# SplitterBoxRevA.net
KiCad netlist of a schematic drawn in EAGLE
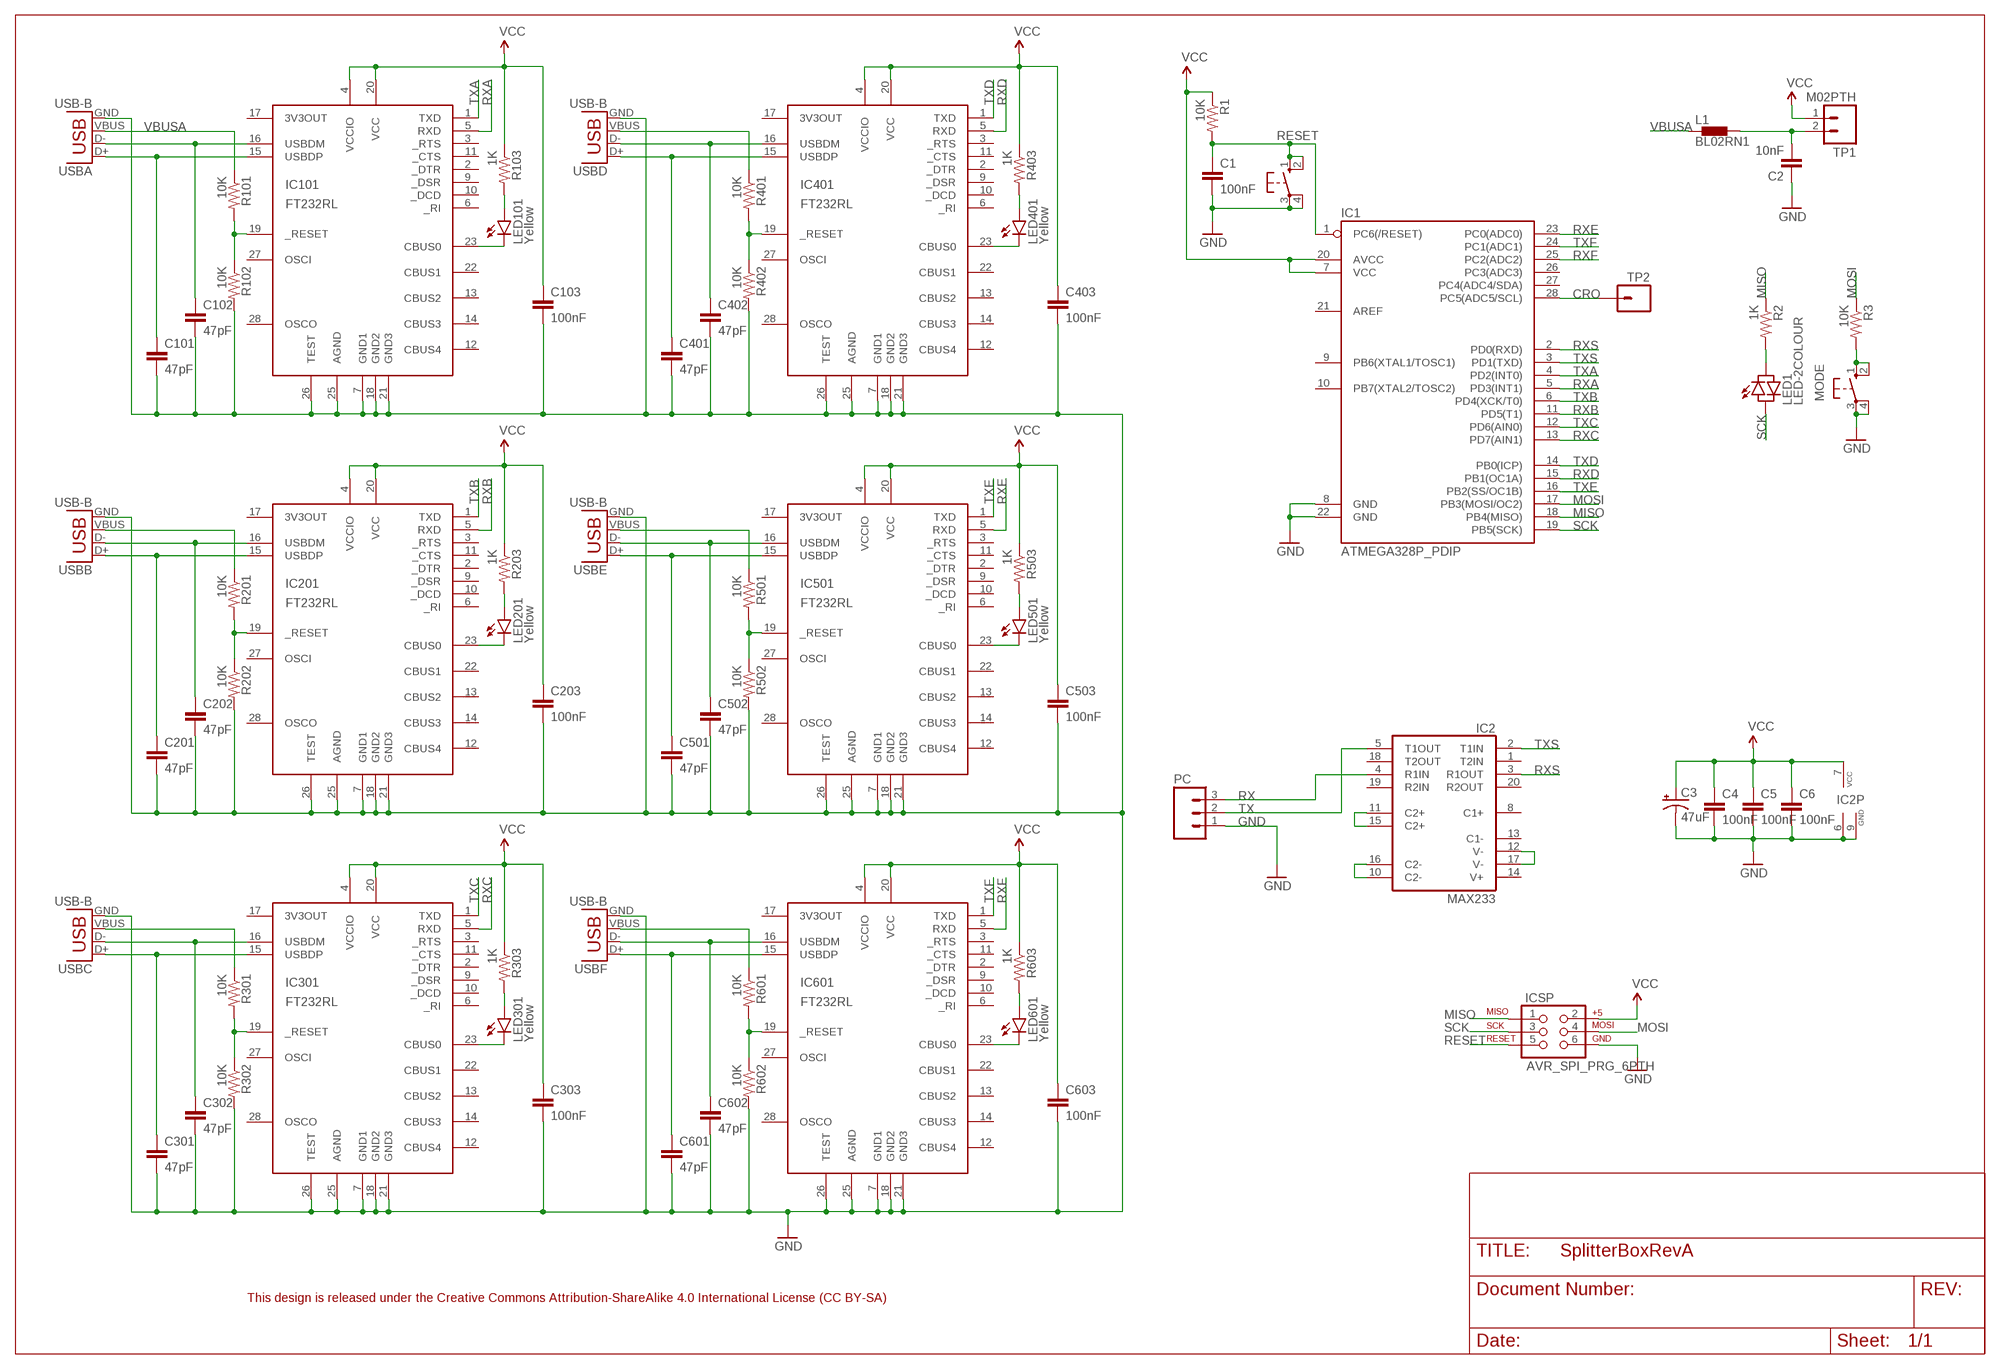
[diagram p0: schematic, sheet 1]

(export (version "E")
  (design (tool "Eeschema 10.0.6"))
  (components
    (comp (ref "C1")
      (value "100nF")
      (footprint "eagle-import:CAP-PTH-SMALL")
      (libsource (lib "eagle-import") (part "CAPPTH"))
    )
    (comp (ref "C2")
      (value "10nF")
      (footprint "eagle-import:CAP-PTH-SMALL")
      (libsource (lib "eagle-import") (part "CAPPTH"))
    )
    (comp (ref "C3")
      (value "47uF")
      (footprint "eagle-import:CPOL-RADIAL-100UF-25V")
      (libsource (lib "eagle-import") (part "CAP_POLPTH1"))
    )
    (comp (ref "C4")
      (value "100nF")
      (footprint "eagle-import:CAP-PTH-SMALL")
      (libsource (lib "eagle-import") (part "CAPPTH"))
    )
    (comp (ref "C5")
      (value "100nF")
      (footprint "eagle-import:CAP-PTH-SMALL")
      (libsource (lib "eagle-import") (part "CAPPTH"))
    )
    (comp (ref "C6")
      (value "100nF")
      (footprint "eagle-import:CAP-PTH-SMALL")
      (libsource (lib "eagle-import") (part "CAPPTH"))
    )
    (comp (ref "C101")
      (value "47pF")
      (footprint "eagle-import:CAP-PTH-SMALL")
      (libsource (lib "eagle-import") (part "CAPPTH"))
    )
    (comp (ref "C102")
      (value "47pF")
      (footprint "eagle-import:CAP-PTH-SMALL")
      (libsource (lib "eagle-import") (part "CAPPTH"))
    )
    (comp (ref "C103")
      (value "100nF")
      (footprint "eagle-import:CAP-PTH-SMALL")
      (libsource (lib "eagle-import") (part "CAPPTH"))
    )
    (comp (ref "C201")
      (value "47pF")
      (footprint "eagle-import:CAP-PTH-SMALL")
      (libsource (lib "eagle-import") (part "CAPPTH"))
    )
    (comp (ref "C202")
      (value "47pF")
      (footprint "eagle-import:CAP-PTH-SMALL")
      (libsource (lib "eagle-import") (part "CAPPTH"))
    )
    (comp (ref "C203")
      (value "100nF")
      (footprint "eagle-import:CAP-PTH-SMALL")
      (libsource (lib "eagle-import") (part "CAPPTH"))
    )
    (comp (ref "C301")
      (value "47pF")
      (footprint "eagle-import:CAP-PTH-SMALL")
      (libsource (lib "eagle-import") (part "CAPPTH"))
    )
    (comp (ref "C302")
      (value "47pF")
      (footprint "eagle-import:CAP-PTH-SMALL")
      (libsource (lib "eagle-import") (part "CAPPTH"))
    )
    (comp (ref "C303")
      (value "100nF")
      (footprint "eagle-import:CAP-PTH-SMALL")
      (libsource (lib "eagle-import") (part "CAPPTH"))
    )
    (comp (ref "C401")
      (value "47pF")
      (footprint "eagle-import:CAP-PTH-SMALL")
      (libsource (lib "eagle-import") (part "CAPPTH"))
    )
    (comp (ref "C402")
      (value "47pF")
      (footprint "eagle-import:CAP-PTH-SMALL")
      (libsource (lib "eagle-import") (part "CAPPTH"))
    )
    (comp (ref "C403")
      (value "100nF")
      (footprint "eagle-import:CAP-PTH-SMALL")
      (libsource (lib "eagle-import") (part "CAPPTH"))
    )
    (comp (ref "C501")
      (value "47pF")
      (footprint "eagle-import:CAP-PTH-SMALL")
      (libsource (lib "eagle-import") (part "CAPPTH"))
    )
    (comp (ref "C502")
      (value "47pF")
      (footprint "eagle-import:CAP-PTH-SMALL")
      (libsource (lib "eagle-import") (part "CAPPTH"))
    )
    (comp (ref "C503")
      (value "100nF")
      (footprint "eagle-import:CAP-PTH-SMALL")
      (libsource (lib "eagle-import") (part "CAPPTH"))
    )
    (comp (ref "C601")
      (value "47pF")
      (footprint "eagle-import:CAP-PTH-SMALL")
      (libsource (lib "eagle-import") (part "CAPPTH"))
    )
    (comp (ref "C602")
      (value "47pF")
      (footprint "eagle-import:CAP-PTH-SMALL")
      (libsource (lib "eagle-import") (part "CAPPTH"))
    )
    (comp (ref "C603")
      (value "100nF")
      (footprint "eagle-import:CAP-PTH-SMALL")
      (libsource (lib "eagle-import") (part "CAPPTH"))
    )
    (comp (ref "IC1")
      (value "ATMEGA328P_PDIP")
      (footprint "eagle-import:DIL28-3")
      (libsource (lib "eagle-import") (part "ATMEGA328P_PDIP"))
    )
    (comp (ref "IC2")
      (value "MAX233")
      (footprint "eagle-import:DIL20")
      (fields (field (name "MPN") "MAX233ACPP+G36"))
      (libsource (lib "eagle-import") (part "MAX233"))
    )
    (comp (ref "IC101")
      (value "FT232RL")
      (footprint "eagle-import:SSOP28DB")
      (libsource (lib "eagle-import") (part "FT232RL"))
    )
    (comp (ref "IC201")
      (value "FT232RL")
      (footprint "eagle-import:SSOP28DB")
      (libsource (lib "eagle-import") (part "FT232RL"))
    )
    (comp (ref "IC301")
      (value "FT232RL")
      (footprint "eagle-import:SSOP28DB")
      (libsource (lib "eagle-import") (part "FT232RL"))
    )
    (comp (ref "IC401")
      (value "FT232RL")
      (footprint "eagle-import:SSOP28DB")
      (libsource (lib "eagle-import") (part "FT232RL"))
    )
    (comp (ref "IC501")
      (value "FT232RL")
      (footprint "eagle-import:SSOP28DB")
      (libsource (lib "eagle-import") (part "FT232RL"))
    )
    (comp (ref "IC601")
      (value "FT232RL")
      (footprint "eagle-import:SSOP28DB")
      (libsource (lib "eagle-import") (part "FT232RL"))
    )
    (comp (ref "ICSP")
      (value "AVR_SPI_PRG_6PTH")
      (footprint "eagle-import:2X3")
      (libsource (lib "eagle-import") (part "AVR_SPI_PRG_6PTH"))
    )
    (comp (ref "L1")
      (value "BL02RN1")
      (footprint "eagle-import:BL02RN1")
      (libsource (lib "eagle-import") (part "BL02RN1"))
    )
    (comp (ref "LED1")
      (value "LED-2COLOUR")
      (footprint "eagle-import:LED3MM")
      (libsource (lib "eagle-import") (part "LED-2COLOUR"))
    )
    (comp (ref "LED101")
      (value "Yellow")
      (footprint "eagle-import:LED3MM_LARGEHOLES")
      (libsource (lib "eagle-import") (part "LED-LH3MM"))
    )
    (comp (ref "LED201")
      (value "Yellow")
      (footprint "eagle-import:LED3MM_LARGEHOLES")
      (libsource (lib "eagle-import") (part "LED-LH3MM"))
    )
    (comp (ref "LED301")
      (value "Yellow")
      (footprint "eagle-import:LED3MM_LARGEHOLES")
      (libsource (lib "eagle-import") (part "LED-LH3MM"))
    )
    (comp (ref "LED401")
      (value "Yellow")
      (footprint "eagle-import:LED3MM_LARGEHOLES")
      (libsource (lib "eagle-import") (part "LED-LH3MM"))
    )
    (comp (ref "LED501")
      (value "Yellow")
      (footprint "eagle-import:LED3MM_LARGEHOLES")
      (libsource (lib "eagle-import") (part "LED-LH3MM"))
    )
    (comp (ref "LED601")
      (value "Yellow")
      (footprint "eagle-import:LED3MM_LARGEHOLES")
      (libsource (lib "eagle-import") (part "LED-LH3MM"))
    )
    (comp (ref "MODE")
      (value "10-XX")
      (footprint "eagle-import:B3F-10XX")
      (fields (field (name "MPN") "B3F-1000"))
      (libsource (lib "eagle-import") (part "10-XX"))
    )
    (comp (ref "PC")
      (value "M03PTH")
      (footprint "eagle-import:1X03")
      (libsource (lib "eagle-import") (part "M03PTH"))
    )
    (comp (ref "R1")
      (value "10K")
      (footprint "eagle-import:AXIAL-0.4")
      (libsource (lib "eagle-import") (part "RESISTORPTH-1/4W"))
    )
    (comp (ref "R2")
      (value "1K")
      (footprint "eagle-import:AXIAL-0.4")
      (libsource (lib "eagle-import") (part "RESISTORPTH-1/4W"))
    )
    (comp (ref "R3")
      (value "10K")
      (footprint "eagle-import:AXIAL-0.4")
      (libsource (lib "eagle-import") (part "RESISTORPTH-1/4W"))
    )
    (comp (ref "R101")
      (value "10K")
      (footprint "eagle-import:AXIAL-0.4")
      (libsource (lib "eagle-import") (part "RESISTORPTH-1/4W"))
    )
    (comp (ref "R102")
      (value "10K")
      (footprint "eagle-import:AXIAL-0.4")
      (libsource (lib "eagle-import") (part "RESISTORPTH-1/4W"))
    )
    (comp (ref "R103")
      (value "1K")
      (footprint "eagle-import:AXIAL-0.4")
      (libsource (lib "eagle-import") (part "RESISTORPTH-1/4W"))
    )
    (comp (ref "R201")
      (value "10K")
      (footprint "eagle-import:AXIAL-0.4")
      (libsource (lib "eagle-import") (part "RESISTORPTH-1/4W"))
    )
    (comp (ref "R202")
      (value "10K")
      (footprint "eagle-import:AXIAL-0.4")
      (libsource (lib "eagle-import") (part "RESISTORPTH-1/4W"))
    )
    (comp (ref "R203")
      (value "1K")
      (footprint "eagle-import:AXIAL-0.4")
      (libsource (lib "eagle-import") (part "RESISTORPTH-1/4W"))
    )
    (comp (ref "R301")
      (value "10K")
      (footprint "eagle-import:AXIAL-0.4")
      (libsource (lib "eagle-import") (part "RESISTORPTH-1/4W"))
    )
    (comp (ref "R302")
      (value "10K")
      (footprint "eagle-import:AXIAL-0.4")
      (libsource (lib "eagle-import") (part "RESISTORPTH-1/4W"))
    )
    (comp (ref "R303")
      (value "1K")
      (footprint "eagle-import:AXIAL-0.4")
      (libsource (lib "eagle-import") (part "RESISTORPTH-1/4W"))
    )
    (comp (ref "R401")
      (value "10K")
      (footprint "eagle-import:AXIAL-0.4")
      (libsource (lib "eagle-import") (part "RESISTORPTH-1/4W"))
    )
    (comp (ref "R402")
      (value "10K")
      (footprint "eagle-import:AXIAL-0.4")
      (libsource (lib "eagle-import") (part "RESISTORPTH-1/4W"))
    )
    (comp (ref "R403")
      (value "1K")
      (footprint "eagle-import:AXIAL-0.4")
      (libsource (lib "eagle-import") (part "RESISTORPTH-1/4W"))
    )
    (comp (ref "R501")
      (value "10K")
      (footprint "eagle-import:AXIAL-0.4")
      (libsource (lib "eagle-import") (part "RESISTORPTH-1/4W"))
    )
    (comp (ref "R502")
      (value "10K")
      (footprint "eagle-import:AXIAL-0.4")
      (libsource (lib "eagle-import") (part "RESISTORPTH-1/4W"))
    )
    (comp (ref "R503")
      (value "1K")
      (footprint "eagle-import:AXIAL-0.4")
      (libsource (lib "eagle-import") (part "RESISTORPTH-1/4W"))
    )
    (comp (ref "R601")
      (value "10K")
      (footprint "eagle-import:AXIAL-0.4")
      (libsource (lib "eagle-import") (part "RESISTORPTH-1/4W"))
    )
    (comp (ref "R602")
      (value "10K")
      (footprint "eagle-import:AXIAL-0.4")
      (libsource (lib "eagle-import") (part "RESISTORPTH-1/4W"))
    )
    (comp (ref "R603")
      (value "1K")
      (footprint "eagle-import:AXIAL-0.4")
      (libsource (lib "eagle-import") (part "RESISTORPTH-1/4W"))
    )
    (comp (ref "RST")
      (value "10-XX")
      (footprint "eagle-import:B3F-10XX")
      (fields (field (name "MPN") "B3F-1000"))
      (libsource (lib "eagle-import") (part "10-XX"))
    )
    (comp (ref "TP1")
      (value "M02PTH")
      (footprint "eagle-import:1X02")
      (libsource (lib "eagle-import") (part "M02PTH"))
    )
    (comp (ref "TP2")
      (value "M01PTH")
      (footprint "eagle-import:1X01")
      (libsource (lib "eagle-import") (part "M01PTH"))
    )
    (comp (ref "USBA")
      (value "USB-B")
      (footprint "eagle-import:USB-B-PTH")
      (libsource (lib "eagle-import") (part "USBPTH"))
    )
    (comp (ref "USBB")
      (value "USB-B")
      (footprint "eagle-import:USB-B-PTH")
      (libsource (lib "eagle-import") (part "USBPTH"))
    )
    (comp (ref "USBC")
      (value "USB-B")
      (footprint "eagle-import:USB-B-PTH")
      (libsource (lib "eagle-import") (part "USBPTH"))
    )
    (comp (ref "USBD")
      (value "USB-B")
      (footprint "eagle-import:USB-B-PTH")
      (libsource (lib "eagle-import") (part "USBPTH"))
    )
    (comp (ref "USBE")
      (value "USB-B")
      (footprint "eagle-import:USB-B-PTH")
      (libsource (lib "eagle-import") (part "USBPTH"))
    )
    (comp (ref "USBF")
      (value "USB-B")
      (footprint "eagle-import:USB-B-PTH")
      (libsource (lib "eagle-import") (part "USBPTH"))
    )
  )
  (nets
    (net (code "1") (name "/CRO") (class "Default")
      (node (ref "IC1") (pin "28") (pinfunction "PC5(ADC5/SCL)_28") (pintype "bidirectional"))
      (node (ref "TP2") (pin "1") (pinfunction "1_1") (pintype "passive"))
    )
    (net (code "2") (name "/MISO") (class "Default")
      (node (ref "IC1") (pin "18") (pinfunction "PB4(MISO)_18") (pintype "bidirectional"))
      (node (ref "ICSP") (pin "1") (pinfunction "1_1") (pintype "passive"))
      (node (ref "R2") (pin "P$1") (pinfunction "1_P$1") (pintype "passive"))
    )
    (net (code "3") (name "/MOSI") (class "Default")
      (node (ref "IC1") (pin "17") (pinfunction "PB3(MOSI/OC2)_17") (pintype "bidirectional"))
      (node (ref "ICSP") (pin "4") (pinfunction "4_4") (pintype "passive"))
      (node (ref "R3") (pin "P$1") (pinfunction "1_P$1") (pintype "passive"))
    )
    (net (code "4") (name "/RESET") (class "Default")
      (node (ref "C1") (pin "1") (pinfunction "1_1") (pintype "passive"))
      (node (ref "IC1") (pin "1") (pinfunction "PC6(/RESET)_1") (pintype "bidirectional"))
      (node (ref "ICSP") (pin "5") (pinfunction "5_5") (pintype "passive"))
      (node (ref "R1") (pin "P$2") (pinfunction "2_P$2") (pintype "passive"))
      (node (ref "RST") (pin "1") (pinfunction "S_1") (pintype "passive"))
      (node (ref "RST") (pin "2") (pinfunction "S1_2") (pintype "passive"))
    )
    (net (code "5") (name "/RX") (class "Default")
      (node (ref "IC2") (pin "4") (pinfunction "R1IN_4") (pintype "input"))
      (node (ref "PC") (pin "3") (pinfunction "3_3") (pintype "passive"))
    )
    (net (code "6") (name "/RXA") (class "Default")
      (node (ref "IC1") (pin "5") (pinfunction "PD3(INT1)_5") (pintype "bidirectional"))
      (node (ref "IC101") (pin "5") (pinfunction "RXD_5") (pintype "input"))
    )
    (net (code "7") (name "/RXB") (class "Default")
      (node (ref "IC1") (pin "11") (pinfunction "PD5(T1)_11") (pintype "bidirectional"))
      (node (ref "IC201") (pin "5") (pinfunction "RXD_5") (pintype "input"))
    )
    (net (code "8") (name "/RXC") (class "Default")
      (node (ref "IC1") (pin "13") (pinfunction "PD7(AIN1)_13") (pintype "bidirectional"))
      (node (ref "IC301") (pin "5") (pinfunction "RXD_5") (pintype "input"))
    )
    (net (code "9") (name "/RXD") (class "Default")
      (node (ref "IC1") (pin "15") (pinfunction "PB1(OC1A)_15") (pintype "bidirectional"))
      (node (ref "IC401") (pin "5") (pinfunction "RXD_5") (pintype "input"))
    )
    (net (code "10") (name "/RXE") (class "Default")
      (node (ref "IC1") (pin "23") (pinfunction "PC0(ADC0)_23") (pintype "bidirectional"))
      (node (ref "IC501") (pin "5") (pinfunction "RXD_5") (pintype "input"))
    )
    (net (code "11") (name "/RXF") (class "Default")
      (node (ref "IC1") (pin "25") (pinfunction "PC2(ADC2)_25") (pintype "bidirectional"))
      (node (ref "IC601") (pin "5") (pinfunction "RXD_5") (pintype "input"))
    )
    (net (code "12") (name "/RXS") (class "Default")
      (node (ref "IC1") (pin "2") (pinfunction "PD0(RXD)_2") (pintype "bidirectional"))
      (node (ref "IC2") (pin "3") (pinfunction "R1OUT_3") (pintype "output"))
    )
    (net (code "13") (name "/SCK") (class "Default")
      (node (ref "IC1") (pin "19") (pinfunction "PB5(SCK)_19") (pintype "bidirectional"))
      (node (ref "ICSP") (pin "3") (pinfunction "3_3") (pintype "passive"))
      (node (ref "LED1") (pin "K") (pinfunction "C_K") (pintype "passive"))
    )
    (net (code "14") (name "/TX") (class "Default")
      (node (ref "IC2") (pin "5") (pinfunction "T1OUT_5") (pintype "output"))
      (node (ref "PC") (pin "2") (pinfunction "2_2") (pintype "passive"))
    )
    (net (code "15") (name "/TXA") (class "Default")
      (node (ref "IC1") (pin "4") (pinfunction "PD2(INT0)_4") (pintype "bidirectional"))
      (node (ref "IC101") (pin "1") (pinfunction "TXD_1") (pintype "output"))
    )
    (net (code "16") (name "/TXB") (class "Default")
      (node (ref "IC1") (pin "6") (pinfunction "PD4(XCK/T0)_6") (pintype "bidirectional"))
      (node (ref "IC201") (pin "1") (pinfunction "TXD_1") (pintype "output"))
    )
    (net (code "17") (name "/TXC") (class "Default")
      (node (ref "IC1") (pin "12") (pinfunction "PD6(AIN0)_12") (pintype "bidirectional"))
      (node (ref "IC301") (pin "1") (pinfunction "TXD_1") (pintype "output"))
    )
    (net (code "18") (name "/TXD") (class "Default")
      (node (ref "IC1") (pin "14") (pinfunction "PB0(ICP)_14") (pintype "bidirectional"))
      (node (ref "IC401") (pin "1") (pinfunction "TXD_1") (pintype "output"))
    )
    (net (code "19") (name "/TXE") (class "Default")
      (node (ref "IC1") (pin "16") (pinfunction "PB2(SS/OC1B)_16") (pintype "bidirectional"))
      (node (ref "IC501") (pin "1") (pinfunction "TXD_1") (pintype "output"))
    )
    (net (code "20") (name "/TXF") (class "Default")
      (node (ref "IC1") (pin "24") (pinfunction "PC1(ADC1)_24") (pintype "bidirectional"))
      (node (ref "IC601") (pin "1") (pinfunction "TXD_1") (pintype "output"))
    )
    (net (code "21") (name "/TXS") (class "Default")
      (node (ref "IC1") (pin "3") (pinfunction "PD1(TXD)_3") (pintype "bidirectional"))
      (node (ref "IC2") (pin "2") (pinfunction "T1IN_2") (pintype "input"))
    )
    (net (code "22") (name "/VBUSA") (class "Default")
      (node (ref "L1") (pin "1") (pinfunction "1_1") (pintype "passive"))
      (node (ref "R101") (pin "P$1") (pinfunction "1_P$1") (pintype "passive"))
      (node (ref "USBA") (pin "VBUS") (pinfunction "VBUS_VBUS") (pintype "bidirectional"))
    )
    (net (code "23") (name "GND") (class "Default")
      (node (ref "C1") (pin "2") (pinfunction "2_2") (pintype "passive"))
      (node (ref "C101") (pin "2") (pinfunction "2_2") (pintype "passive"))
      (node (ref "C102") (pin "2") (pinfunction "2_2") (pintype "passive"))
      (node (ref "C103") (pin "2") (pinfunction "2_2") (pintype "passive"))
      (node (ref "C2") (pin "1") (pinfunction "1_1") (pintype "passive"))
      (node (ref "C201") (pin "2") (pinfunction "2_2") (pintype "passive"))
      (node (ref "C202") (pin "2") (pinfunction "2_2") (pintype "passive"))
      (node (ref "C203") (pin "2") (pinfunction "2_2") (pintype "passive"))
      (node (ref "C3") (pin "2") (pinfunction "-_2") (pintype "passive"))
      (node (ref "C301") (pin "2") (pinfunction "2_2") (pintype "passive"))
      (node (ref "C302") (pin "2") (pinfunction "2_2") (pintype "passive"))
      (node (ref "C303") (pin "2") (pinfunction "2_2") (pintype "passive"))
      (node (ref "C4") (pin "2") (pinfunction "2_2") (pintype "passive"))
      (node (ref "C401") (pin "2") (pinfunction "2_2") (pintype "passive"))
      (node (ref "C402") (pin "2") (pinfunction "2_2") (pintype "passive"))
      (node (ref "C403") (pin "2") (pinfunction "2_2") (pintype "passive"))
      (node (ref "C5") (pin "2") (pinfunction "2_2") (pintype "passive"))
      (node (ref "C501") (pin "2") (pinfunction "2_2") (pintype "passive"))
      (node (ref "C502") (pin "2") (pinfunction "2_2") (pintype "passive"))
      (node (ref "C503") (pin "2") (pinfunction "2_2") (pintype "passive"))
      (node (ref "C6") (pin "2") (pinfunction "2_2") (pintype "passive"))
      (node (ref "C601") (pin "2") (pinfunction "2_2") (pintype "passive"))
      (node (ref "C602") (pin "2") (pinfunction "2_2") (pintype "passive"))
      (node (ref "C603") (pin "2") (pinfunction "2_2") (pintype "passive"))
      (node (ref "IC1") (pin "22") (pinfunction "GND_22") (pintype "bidirectional"))
      (node (ref "IC1") (pin "8") (pinfunction "GND_8") (pintype "bidirectional"))
      (node (ref "IC101") (pin "18") (pinfunction "GND2_18") (pintype "power_in"))
      (node (ref "IC101") (pin "21") (pinfunction "GND3_21") (pintype "power_in"))
      (node (ref "IC101") (pin "25") (pinfunction "AGND_25") (pintype "power_in"))
      (node (ref "IC101") (pin "26") (pinfunction "TEST_26") (pintype "input"))
      (node (ref "IC101") (pin "7") (pinfunction "GND1_7") (pintype "power_in"))
      (node (ref "IC2") (pin "6") (pinfunction "GND_6") (pintype "power_in"))
      (node (ref "IC2") (pin "9") (pinfunction "GND_9") (pintype "power_in"))
      (node (ref "IC201") (pin "18") (pinfunction "GND2_18") (pintype "power_in"))
      (node (ref "IC201") (pin "21") (pinfunction "GND3_21") (pintype "power_in"))
      (node (ref "IC201") (pin "25") (pinfunction "AGND_25") (pintype "power_in"))
      (node (ref "IC201") (pin "26") (pinfunction "TEST_26") (pintype "input"))
      (node (ref "IC201") (pin "7") (pinfunction "GND1_7") (pintype "power_in"))
      (node (ref "IC301") (pin "18") (pinfunction "GND2_18") (pintype "power_in"))
      (node (ref "IC301") (pin "21") (pinfunction "GND3_21") (pintype "power_in"))
      (node (ref "IC301") (pin "25") (pinfunction "AGND_25") (pintype "power_in"))
      (node (ref "IC301") (pin "26") (pinfunction "TEST_26") (pintype "input"))
      (node (ref "IC301") (pin "7") (pinfunction "GND1_7") (pintype "power_in"))
      (node (ref "IC401") (pin "18") (pinfunction "GND2_18") (pintype "power_in"))
      (node (ref "IC401") (pin "21") (pinfunction "GND3_21") (pintype "power_in"))
      (node (ref "IC401") (pin "25") (pinfunction "AGND_25") (pintype "power_in"))
      (node (ref "IC401") (pin "26") (pinfunction "TEST_26") (pintype "input"))
      (node (ref "IC401") (pin "7") (pinfunction "GND1_7") (pintype "power_in"))
      (node (ref "IC501") (pin "18") (pinfunction "GND2_18") (pintype "power_in"))
      (node (ref "IC501") (pin "21") (pinfunction "GND3_21") (pintype "power_in"))
      (node (ref "IC501") (pin "25") (pinfunction "AGND_25") (pintype "power_in"))
      (node (ref "IC501") (pin "26") (pinfunction "TEST_26") (pintype "input"))
      (node (ref "IC501") (pin "7") (pinfunction "GND1_7") (pintype "power_in"))
      (node (ref "IC601") (pin "18") (pinfunction "GND2_18") (pintype "power_in"))
      (node (ref "IC601") (pin "21") (pinfunction "GND3_21") (pintype "power_in"))
      (node (ref "IC601") (pin "25") (pinfunction "AGND_25") (pintype "power_in"))
      (node (ref "IC601") (pin "26") (pinfunction "TEST_26") (pintype "input"))
      (node (ref "IC601") (pin "7") (pinfunction "GND1_7") (pintype "power_in"))
      (node (ref "ICSP") (pin "6") (pinfunction "6_6") (pintype "passive"))
      (node (ref "MODE") (pin "3") (pinfunction "P_3") (pintype "passive"))
      (node (ref "MODE") (pin "4") (pinfunction "P1_4") (pintype "passive"))
      (node (ref "PC") (pin "1") (pinfunction "1_1") (pintype "passive"))
      (node (ref "R102") (pin "P$2") (pinfunction "2_P$2") (pintype "passive"))
      (node (ref "R202") (pin "P$2") (pinfunction "2_P$2") (pintype "passive"))
      (node (ref "R302") (pin "P$2") (pinfunction "2_P$2") (pintype "passive"))
      (node (ref "R402") (pin "P$2") (pinfunction "2_P$2") (pintype "passive"))
      (node (ref "R502") (pin "P$2") (pinfunction "2_P$2") (pintype "passive"))
      (node (ref "R602") (pin "P$2") (pinfunction "2_P$2") (pintype "passive"))
      (node (ref "RST") (pin "3") (pinfunction "P_3") (pintype "passive"))
      (node (ref "RST") (pin "4") (pinfunction "P1_4") (pintype "passive"))
      (node (ref "USBA") (pin "GND") (pinfunction "GND_GND") (pintype "bidirectional"))
      (node (ref "USBB") (pin "GND") (pinfunction "GND_GND") (pintype "bidirectional"))
      (node (ref "USBC") (pin "GND") (pinfunction "GND_GND") (pintype "bidirectional"))
      (node (ref "USBD") (pin "GND") (pinfunction "GND_GND") (pintype "bidirectional"))
      (node (ref "USBE") (pin "GND") (pinfunction "GND_GND") (pintype "bidirectional"))
      (node (ref "USBF") (pin "GND") (pinfunction "GND_GND") (pintype "bidirectional"))
    )
    (net (code "24") (name "Net-(C2-Pad2)") (class "Default")
      (node (ref "C2") (pin "2") (pinfunction "2_2") (pintype "passive"))
      (node (ref "L1") (pin "2") (pinfunction "2_2") (pintype "passive"))
      (node (ref "TP1") (pin "2") (pinfunction "2_2") (pintype "passive"))
    )
    (net (code "25") (name "Net-(IC2A-C2+-Pad11)") (class "Default")
      (node (ref "IC2") (pin "11") (pinfunction "C2+_11") (pintype "bidirectional"))
      (node (ref "IC2") (pin "15") (pinfunction "C2+_15") (pintype "bidirectional"))
    )
    (net (code "26") (name "Net-(IC2A-C2--Pad10)") (class "Default")
      (node (ref "IC2") (pin "10") (pinfunction "C2-_10") (pintype "bidirectional"))
      (node (ref "IC2") (pin "16") (pinfunction "C2-_16") (pintype "bidirectional"))
    )
    (net (code "27") (name "Net-(IC2A-V--Pad12)") (class "Default")
      (node (ref "IC2") (pin "12") (pinfunction "V-_12") (pintype "bidirectional"))
      (node (ref "IC2") (pin "17") (pinfunction "V-_17") (pintype "bidirectional"))
    )
    (net (code "28") (name "Net-(IC101-CBUS0)") (class "Default")
      (node (ref "IC101") (pin "23") (pinfunction "CBUS0_23") (pintype "bidirectional"))
      (node (ref "LED101") (pin "K") (pinfunction "C_K") (pintype "passive"))
    )
    (net (code "29") (name "Net-(IC101-USBDM)") (class "Default")
      (node (ref "C102") (pin "1") (pinfunction "1_1") (pintype "passive"))
      (node (ref "IC101") (pin "16") (pinfunction "USBDM_16") (pintype "bidirectional"))
      (node (ref "USBA") (pin "D-") (pinfunction "D-_D-") (pintype "bidirectional"))
    )
    (net (code "30") (name "Net-(IC101-USBDP)") (class "Default")
      (node (ref "C101") (pin "1") (pinfunction "1_1") (pintype "passive"))
      (node (ref "IC101") (pin "15") (pinfunction "USBDP_15") (pintype "bidirectional"))
      (node (ref "USBA") (pin "D+") (pinfunction "D+_D+") (pintype "bidirectional"))
    )
    (net (code "31") (name "Net-(IC101-_RESET)") (class "Default")
      (node (ref "IC101") (pin "19") (pinfunction "_RESET_19") (pintype "input"))
      (node (ref "R101") (pin "P$2") (pinfunction "2_P$2") (pintype "passive"))
      (node (ref "R102") (pin "P$1") (pinfunction "1_P$1") (pintype "passive"))
    )
    (net (code "32") (name "Net-(IC201-CBUS0)") (class "Default")
      (node (ref "IC201") (pin "23") (pinfunction "CBUS0_23") (pintype "bidirectional"))
      (node (ref "LED201") (pin "K") (pinfunction "C_K") (pintype "passive"))
    )
    (net (code "33") (name "Net-(IC201-USBDM)") (class "Default")
      (node (ref "C202") (pin "1") (pinfunction "1_1") (pintype "passive"))
      (node (ref "IC201") (pin "16") (pinfunction "USBDM_16") (pintype "bidirectional"))
      (node (ref "USBB") (pin "D-") (pinfunction "D-_D-") (pintype "bidirectional"))
    )
    (net (code "34") (name "Net-(IC201-USBDP)") (class "Default")
      (node (ref "C201") (pin "1") (pinfunction "1_1") (pintype "passive"))
      (node (ref "IC201") (pin "15") (pinfunction "USBDP_15") (pintype "bidirectional"))
      (node (ref "USBB") (pin "D+") (pinfunction "D+_D+") (pintype "bidirectional"))
    )
    (net (code "35") (name "Net-(IC201-_RESET)") (class "Default")
      (node (ref "IC201") (pin "19") (pinfunction "_RESET_19") (pintype "input"))
      (node (ref "R201") (pin "P$2") (pinfunction "2_P$2") (pintype "passive"))
      (node (ref "R202") (pin "P$1") (pinfunction "1_P$1") (pintype "passive"))
    )
    (net (code "36") (name "Net-(IC301-CBUS0)") (class "Default")
      (node (ref "IC301") (pin "23") (pinfunction "CBUS0_23") (pintype "bidirectional"))
      (node (ref "LED301") (pin "K") (pinfunction "C_K") (pintype "passive"))
    )
    (net (code "37") (name "Net-(IC301-USBDM)") (class "Default")
      (node (ref "C302") (pin "1") (pinfunction "1_1") (pintype "passive"))
      (node (ref "IC301") (pin "16") (pinfunction "USBDM_16") (pintype "bidirectional"))
      (node (ref "USBC") (pin "D-") (pinfunction "D-_D-") (pintype "bidirectional"))
    )
    (net (code "38") (name "Net-(IC301-USBDP)") (class "Default")
      (node (ref "C301") (pin "1") (pinfunction "1_1") (pintype "passive"))
      (node (ref "IC301") (pin "15") (pinfunction "USBDP_15") (pintype "bidirectional"))
      (node (ref "USBC") (pin "D+") (pinfunction "D+_D+") (pintype "bidirectional"))
    )
    (net (code "39") (name "Net-(IC301-_RESET)") (class "Default")
      (node (ref "IC301") (pin "19") (pinfunction "_RESET_19") (pintype "input"))
      (node (ref "R301") (pin "P$2") (pinfunction "2_P$2") (pintype "passive"))
      (node (ref "R302") (pin "P$1") (pinfunction "1_P$1") (pintype "passive"))
    )
    (net (code "40") (name "Net-(IC401-CBUS0)") (class "Default")
      (node (ref "IC401") (pin "23") (pinfunction "CBUS0_23") (pintype "bidirectional"))
      (node (ref "LED401") (pin "K") (pinfunction "C_K") (pintype "passive"))
    )
    (net (code "41") (name "Net-(IC401-USBDM)") (class "Default")
      (node (ref "C402") (pin "1") (pinfunction "1_1") (pintype "passive"))
      (node (ref "IC401") (pin "16") (pinfunction "USBDM_16") (pintype "bidirectional"))
      (node (ref "USBD") (pin "D-") (pinfunction "D-_D-") (pintype "bidirectional"))
    )
    (net (code "42") (name "Net-(IC401-USBDP)") (class "Default")
      (node (ref "C401") (pin "1") (pinfunction "1_1") (pintype "passive"))
      (node (ref "IC401") (pin "15") (pinfunction "USBDP_15") (pintype "bidirectional"))
      (node (ref "USBD") (pin "D+") (pinfunction "D+_D+") (pintype "bidirectional"))
    )
    (net (code "43") (name "Net-(IC401-_RESET)") (class "Default")
      (node (ref "IC401") (pin "19") (pinfunction "_RESET_19") (pintype "input"))
      (node (ref "R401") (pin "P$2") (pinfunction "2_P$2") (pintype "passive"))
      (node (ref "R402") (pin "P$1") (pinfunction "1_P$1") (pintype "passive"))
    )
    (net (code "44") (name "Net-(IC501-CBUS0)") (class "Default")
      (node (ref "IC501") (pin "23") (pinfunction "CBUS0_23") (pintype "bidirectional"))
      (node (ref "LED501") (pin "K") (pinfunction "C_K") (pintype "passive"))
    )
    (net (code "45") (name "Net-(IC501-USBDM)") (class "Default")
      (node (ref "C502") (pin "1") (pinfunction "1_1") (pintype "passive"))
      (node (ref "IC501") (pin "16") (pinfunction "USBDM_16") (pintype "bidirectional"))
      (node (ref "USBE") (pin "D-") (pinfunction "D-_D-") (pintype "bidirectional"))
    )
    (net (code "46") (name "Net-(IC501-USBDP)") (class "Default")
      (node (ref "C501") (pin "1") (pinfunction "1_1") (pintype "passive"))
      (node (ref "IC501") (pin "15") (pinfunction "USBDP_15") (pintype "bidirectional"))
      (node (ref "USBE") (pin "D+") (pinfunction "D+_D+") (pintype "bidirectional"))
    )
    (net (code "47") (name "Net-(IC501-_RESET)") (class "Default")
      (node (ref "IC501") (pin "19") (pinfunction "_RESET_19") (pintype "input"))
      (node (ref "R501") (pin "P$2") (pinfunction "2_P$2") (pintype "passive"))
      (node (ref "R502") (pin "P$1") (pinfunction "1_P$1") (pintype "passive"))
    )
    (net (code "48") (name "Net-(IC601-CBUS0)") (class "Default")
      (node (ref "IC601") (pin "23") (pinfunction "CBUS0_23") (pintype "bidirectional"))
      (node (ref "LED601") (pin "K") (pinfunction "C_K") (pintype "passive"))
    )
    (net (code "49") (name "Net-(IC601-USBDM)") (class "Default")
      (node (ref "C602") (pin "1") (pinfunction "1_1") (pintype "passive"))
      (node (ref "IC601") (pin "16") (pinfunction "USBDM_16") (pintype "bidirectional"))
      (node (ref "USBF") (pin "D-") (pinfunction "D-_D-") (pintype "bidirectional"))
    )
    (net (code "50") (name "Net-(IC601-USBDP)") (class "Default")
      (node (ref "C601") (pin "1") (pinfunction "1_1") (pintype "passive"))
      (node (ref "IC601") (pin "15") (pinfunction "USBDP_15") (pintype "bidirectional"))
      (node (ref "USBF") (pin "D+") (pinfunction "D+_D+") (pintype "bidirectional"))
    )
    (net (code "51") (name "Net-(IC601-_RESET)") (class "Default")
      (node (ref "IC601") (pin "19") (pinfunction "_RESET_19") (pintype "input"))
      (node (ref "R601") (pin "P$2") (pinfunction "2_P$2") (pintype "passive"))
      (node (ref "R602") (pin "P$1") (pinfunction "1_P$1") (pintype "passive"))
    )
    (net (code "52") (name "Net-(MODE-S)") (class "Default")
      (node (ref "MODE") (pin "1") (pinfunction "S_1") (pintype "passive"))
      (node (ref "MODE") (pin "2") (pinfunction "S1_2") (pintype "passive"))
      (node (ref "R3") (pin "P$2") (pinfunction "2_P$2") (pintype "passive"))
    )
    (net (code "53") (name "Net-(R2-2)") (class "Default")
      (node (ref "LED1") (pin "A") (pinfunction "A_A") (pintype "passive"))
      (node (ref "R2") (pin "P$2") (pinfunction "2_P$2") (pintype "passive"))
    )
    (net (code "54") (name "Net-(R103-2)") (class "Default")
      (node (ref "LED101") (pin "A") (pinfunction "A_A") (pintype "passive"))
      (node (ref "R103") (pin "P$2") (pinfunction "2_P$2") (pintype "passive"))
    )
    (net (code "55") (name "Net-(R201-1)") (class "Default")
      (node (ref "R201") (pin "P$1") (pinfunction "1_P$1") (pintype "passive"))
      (node (ref "USBB") (pin "VBUS") (pinfunction "VBUS_VBUS") (pintype "bidirectional"))
    )
    (net (code "56") (name "Net-(R203-2)") (class "Default")
      (node (ref "LED201") (pin "A") (pinfunction "A_A") (pintype "passive"))
      (node (ref "R203") (pin "P$2") (pinfunction "2_P$2") (pintype "passive"))
    )
    (net (code "57") (name "Net-(R301-1)") (class "Default")
      (node (ref "R301") (pin "P$1") (pinfunction "1_P$1") (pintype "passive"))
      (node (ref "USBC") (pin "VBUS") (pinfunction "VBUS_VBUS") (pintype "bidirectional"))
    )
    (net (code "58") (name "Net-(R303-2)") (class "Default")
      (node (ref "LED301") (pin "A") (pinfunction "A_A") (pintype "passive"))
      (node (ref "R303") (pin "P$2") (pinfunction "2_P$2") (pintype "passive"))
    )
    (net (code "59") (name "Net-(R401-1)") (class "Default")
      (node (ref "R401") (pin "P$1") (pinfunction "1_P$1") (pintype "passive"))
      (node (ref "USBD") (pin "VBUS") (pinfunction "VBUS_VBUS") (pintype "bidirectional"))
    )
    (net (code "60") (name "Net-(R403-2)") (class "Default")
      (node (ref "LED401") (pin "A") (pinfunction "A_A") (pintype "passive"))
      (node (ref "R403") (pin "P$2") (pinfunction "2_P$2") (pintype "passive"))
    )
    (net (code "61") (name "Net-(R501-1)") (class "Default")
      (node (ref "R501") (pin "P$1") (pinfunction "1_P$1") (pintype "passive"))
      (node (ref "USBE") (pin "VBUS") (pinfunction "VBUS_VBUS") (pintype "bidirectional"))
    )
    (net (code "62") (name "Net-(R503-2)") (class "Default")
      (node (ref "LED501") (pin "A") (pinfunction "A_A") (pintype "passive"))
      (node (ref "R503") (pin "P$2") (pinfunction "2_P$2") (pintype "passive"))
    )
    (net (code "63") (name "Net-(R601-1)") (class "Default")
      (node (ref "R601") (pin "P$1") (pinfunction "1_P$1") (pintype "passive"))
      (node (ref "USBF") (pin "VBUS") (pinfunction "VBUS_VBUS") (pintype "bidirectional"))
    )
    (net (code "64") (name "Net-(R603-2)") (class "Default")
      (node (ref "LED601") (pin "A") (pinfunction "A_A") (pintype "passive"))
      (node (ref "R603") (pin "P$2") (pinfunction "2_P$2") (pintype "passive"))
    )
    (net (code "65") (name "VCC") (class "Default")
      (node (ref "C103") (pin "1") (pinfunction "1_1") (pintype "passive"))
      (node (ref "C203") (pin "1") (pinfunction "1_1") (pintype "passive"))
      (node (ref "C3") (pin "1") (pinfunction "+_1") (pintype "passive"))
      (node (ref "C303") (pin "1") (pinfunction "1_1") (pintype "passive"))
      (node (ref "C4") (pin "1") (pinfunction "1_1") (pintype "passive"))
      (node (ref "C403") (pin "1") (pinfunction "1_1") (pintype "passive"))
      (node (ref "C5") (pin "1") (pinfunction "1_1") (pintype "passive"))
      (node (ref "C503") (pin "1") (pinfunction "1_1") (pintype "passive"))
      (node (ref "C6") (pin "1") (pinfunction "1_1") (pintype "passive"))
      (node (ref "C603") (pin "1") (pinfunction "1_1") (pintype "passive"))
      (node (ref "IC1") (pin "20") (pinfunction "AVCC_20") (pintype "bidirectional"))
      (node (ref "IC1") (pin "7") (pinfunction "VCC_7") (pintype "bidirectional"))
      (node (ref "IC101") (pin "20") (pinfunction "VCC_20") (pintype "power_in"))
      (node (ref "IC101") (pin "4") (pinfunction "VCCIO_4") (pintype "power_in"))
      (node (ref "IC2") (pin "7") (pinfunction "VCC_7") (pintype "power_in"))
      (node (ref "IC201") (pin "20") (pinfunction "VCC_20") (pintype "power_in"))
      (node (ref "IC201") (pin "4") (pinfunction "VCCIO_4") (pintype "power_in"))
      (node (ref "IC301") (pin "20") (pinfunction "VCC_20") (pintype "power_in"))
      (node (ref "IC301") (pin "4") (pinfunction "VCCIO_4") (pintype "power_in"))
      (node (ref "IC401") (pin "20") (pinfunction "VCC_20") (pintype "power_in"))
      (node (ref "IC401") (pin "4") (pinfunction "VCCIO_4") (pintype "power_in"))
      (node (ref "IC501") (pin "20") (pinfunction "VCC_20") (pintype "power_in"))
      (node (ref "IC501") (pin "4") (pinfunction "VCCIO_4") (pintype "power_in"))
      (node (ref "IC601") (pin "20") (pinfunction "VCC_20") (pintype "power_in"))
      (node (ref "IC601") (pin "4") (pinfunction "VCCIO_4") (pintype "power_in"))
      (node (ref "ICSP") (pin "2") (pinfunction "2_2") (pintype "passive"))
      (node (ref "R1") (pin "P$1") (pinfunction "1_P$1") (pintype "passive"))
      (node (ref "R103") (pin "P$1") (pinfunction "1_P$1") (pintype "passive"))
      (node (ref "R203") (pin "P$1") (pinfunction "1_P$1") (pintype "passive"))
      (node (ref "R303") (pin "P$1") (pinfunction "1_P$1") (pintype "passive"))
      (node (ref "R403") (pin "P$1") (pinfunction "1_P$1") (pintype "passive"))
      (node (ref "R503") (pin "P$1") (pinfunction "1_P$1") (pintype "passive"))
      (node (ref "R603") (pin "P$1") (pinfunction "1_P$1") (pintype "passive"))
      (node (ref "TP1") (pin "1") (pinfunction "1_1") (pintype "passive"))
    )
    (net (code "66") (name "unconnected-(IC1-AREF-Pad21)") (class "Default")
      (node (ref "IC1") (pin "21") (pinfunction "AREF_21") (pintype "bidirectional"))
    )
    (net (code "67") (name "unconnected-(IC1-PB6(XTAL1{slash}TOSC1)-Pad9)") (class "Default")
      (node (ref "IC1") (pin "9") (pinfunction "PB6(XTAL1/TOSC1)_9") (pintype "bidirectional"))
    )
    (net (code "68") (name "unconnected-(IC1-PB7(XTAL2{slash}TOSC2)-Pad10)") (class "Default")
      (node (ref "IC1") (pin "10") (pinfunction "PB7(XTAL2/TOSC2)_10") (pintype "bidirectional"))
    )
    (net (code "69") (name "unconnected-(IC1-PC3(ADC3)-Pad26)") (class "Default")
      (node (ref "IC1") (pin "26") (pinfunction "PC3(ADC3)_26") (pintype "bidirectional"))
    )
    (net (code "70") (name "unconnected-(IC1-PC4(ADC4{slash}SDA)-Pad27)") (class "Default")
      (node (ref "IC1") (pin "27") (pinfunction "PC4(ADC4/SDA)_27") (pintype "bidirectional"))
    )
    (net (code "71") (name "unconnected-(IC2A-C1+-Pad8)") (class "Default")
      (node (ref "IC2") (pin "8") (pinfunction "C1+_8") (pintype "bidirectional"))
    )
    (net (code "72") (name "unconnected-(IC2A-C1--Pad13)") (class "Default")
      (node (ref "IC2") (pin "13") (pinfunction "C1-_13") (pintype "bidirectional"))
    )
    (net (code "73") (name "unconnected-(IC2A-R2IN-Pad19)") (class "Default")
      (node (ref "IC2") (pin "19") (pinfunction "R2IN_19") (pintype "input"))
    )
    (net (code "74") (name "unconnected-(IC2A-R2OUT-Pad20)") (class "Default")
      (node (ref "IC2") (pin "20") (pinfunction "R2OUT_20") (pintype "output"))
    )
    (net (code "75") (name "unconnected-(IC2A-T2IN-Pad1)") (class "Default")
      (node (ref "IC2") (pin "1") (pinfunction "T2IN_1") (pintype "input"))
    )
    (net (code "76") (name "unconnected-(IC2A-T2OUT-Pad18)") (class "Default")
      (node (ref "IC2") (pin "18") (pinfunction "T2OUT_18") (pintype "output"))
    )
    (net (code "77") (name "unconnected-(IC2A-V+-Pad14)") (class "Default")
      (node (ref "IC2") (pin "14") (pinfunction "V+_14") (pintype "bidirectional"))
    )
    (net (code "78") (name "unconnected-(IC101-3V3OUT-Pad17)") (class "Default")
      (node (ref "IC101") (pin "17") (pinfunction "3V3OUT_17") (pintype "output"))
    )
    (net (code "79") (name "unconnected-(IC101-CBUS1-Pad22)") (class "Default")
      (node (ref "IC101") (pin "22") (pinfunction "CBUS1_22") (pintype "bidirectional"))
    )
    (net (code "80") (name "unconnected-(IC101-CBUS2-Pad13)") (class "Default")
      (node (ref "IC101") (pin "13") (pinfunction "CBUS2_13") (pintype "bidirectional"))
    )
    (net (code "81") (name "unconnected-(IC101-CBUS3-Pad14)") (class "Default")
      (node (ref "IC101") (pin "14") (pinfunction "CBUS3_14") (pintype "bidirectional"))
    )
    (net (code "82") (name "unconnected-(IC101-CBUS4-Pad12)") (class "Default")
      (node (ref "IC101") (pin "12") (pinfunction "CBUS4_12") (pintype "bidirectional"))
    )
    (net (code "83") (name "unconnected-(IC101-OSCI-Pad27)") (class "Default")
      (node (ref "IC101") (pin "27") (pinfunction "OSCI_27") (pintype "input"))
    )
    (net (code "84") (name "unconnected-(IC101-OSCO-Pad28)") (class "Default")
      (node (ref "IC101") (pin "28") (pinfunction "OSCO_28") (pintype "output"))
    )
    (net (code "85") (name "unconnected-(IC101-_CTS-Pad11)") (class "Default")
      (node (ref "IC101") (pin "11") (pinfunction "_CTS_11") (pintype "input"))
    )
    (net (code "86") (name "unconnected-(IC101-_DCD-Pad10)") (class "Default")
      (node (ref "IC101") (pin "10") (pinfunction "_DCD_10") (pintype "input"))
    )
    (net (code "87") (name "unconnected-(IC101-_DSR-Pad9)") (class "Default")
      (node (ref "IC101") (pin "9") (pinfunction "_DSR_9") (pintype "input"))
    )
    (net (code "88") (name "unconnected-(IC101-_DTR-Pad2)") (class "Default")
      (node (ref "IC101") (pin "2") (pinfunction "_DTR_2") (pintype "output"))
    )
    (net (code "89") (name "unconnected-(IC101-_RI-Pad6)") (class "Default")
      (node (ref "IC101") (pin "6") (pinfunction "_RI_6") (pintype "input"))
    )
    (net (code "90") (name "unconnected-(IC101-_RTS-Pad3)") (class "Default")
      (node (ref "IC101") (pin "3") (pinfunction "_RTS_3") (pintype "output"))
    )
    (net (code "91") (name "unconnected-(IC201-3V3OUT-Pad17)") (class "Default")
      (node (ref "IC201") (pin "17") (pinfunction "3V3OUT_17") (pintype "output"))
    )
    (net (code "92") (name "unconnected-(IC201-CBUS1-Pad22)") (class "Default")
      (node (ref "IC201") (pin "22") (pinfunction "CBUS1_22") (pintype "bidirectional"))
    )
    (net (code "93") (name "unconnected-(IC201-CBUS2-Pad13)") (class "Default")
      (node (ref "IC201") (pin "13") (pinfunction "CBUS2_13") (pintype "bidirectional"))
    )
    (net (code "94") (name "unconnected-(IC201-CBUS3-Pad14)") (class "Default")
      (node (ref "IC201") (pin "14") (pinfunction "CBUS3_14") (pintype "bidirectional"))
    )
    (net (code "95") (name "unconnected-(IC201-CBUS4-Pad12)") (class "Default")
      (node (ref "IC201") (pin "12") (pinfunction "CBUS4_12") (pintype "bidirectional"))
    )
    (net (code "96") (name "unconnected-(IC201-OSCI-Pad27)") (class "Default")
      (node (ref "IC201") (pin "27") (pinfunction "OSCI_27") (pintype "input"))
    )
    (net (code "97") (name "unconnected-(IC201-OSCO-Pad28)") (class "Default")
      (node (ref "IC201") (pin "28") (pinfunction "OSCO_28") (pintype "output"))
    )
    (net (code "98") (name "unconnected-(IC201-_CTS-Pad11)") (class "Default")
      (node (ref "IC201") (pin "11") (pinfunction "_CTS_11") (pintype "input"))
    )
    (net (code "99") (name "unconnected-(IC201-_DCD-Pad10)") (class "Default")
      (node (ref "IC201") (pin "10") (pinfunction "_DCD_10") (pintype "input"))
    )
    (net (code "100") (name "unconnected-(IC201-_DSR-Pad9)") (class "Default")
      (node (ref "IC201") (pin "9") (pinfunction "_DSR_9") (pintype "input"))
    )
    (net (code "101") (name "unconnected-(IC201-_DTR-Pad2)") (class "Default")
      (node (ref "IC201") (pin "2") (pinfunction "_DTR_2") (pintype "output"))
    )
    (net (code "102") (name "unconnected-(IC201-_RI-Pad6)") (class "Default")
      (node (ref "IC201") (pin "6") (pinfunction "_RI_6") (pintype "input"))
    )
    (net (code "103") (name "unconnected-(IC201-_RTS-Pad3)") (class "Default")
      (node (ref "IC201") (pin "3") (pinfunction "_RTS_3") (pintype "output"))
    )
    (net (code "104") (name "unconnected-(IC301-3V3OUT-Pad17)") (class "Default")
      (node (ref "IC301") (pin "17") (pinfunction "3V3OUT_17") (pintype "output"))
    )
    (net (code "105") (name "unconnected-(IC301-CBUS1-Pad22)") (class "Default")
      (node (ref "IC301") (pin "22") (pinfunction "CBUS1_22") (pintype "bidirectional"))
    )
    (net (code "106") (name "unconnected-(IC301-CBUS2-Pad13)") (class "Default")
      (node (ref "IC301") (pin "13") (pinfunction "CBUS2_13") (pintype "bidirectional"))
    )
    (net (code "107") (name "unconnected-(IC301-CBUS3-Pad14)") (class "Default")
      (node (ref "IC301") (pin "14") (pinfunction "CBUS3_14") (pintype "bidirectional"))
    )
    (net (code "108") (name "unconnected-(IC301-CBUS4-Pad12)") (class "Default")
      (node (ref "IC301") (pin "12") (pinfunction "CBUS4_12") (pintype "bidirectional"))
    )
    (net (code "109") (name "unconnected-(IC301-OSCI-Pad27)") (class "Default")
      (node (ref "IC301") (pin "27") (pinfunction "OSCI_27") (pintype "input"))
    )
    (net (code "110") (name "unconnected-(IC301-OSCO-Pad28)") (class "Default")
      (node (ref "IC301") (pin "28") (pinfunction "OSCO_28") (pintype "output"))
    )
    (net (code "111") (name "unconnected-(IC301-_CTS-Pad11)") (class "Default")
      (node (ref "IC301") (pin "11") (pinfunction "_CTS_11") (pintype "input"))
    )
    (net (code "112") (name "unconnected-(IC301-_DCD-Pad10)") (class "Default")
      (node (ref "IC301") (pin "10") (pinfunction "_DCD_10") (pintype "input"))
    )
    (net (code "113") (name "unconnected-(IC301-_DSR-Pad9)") (class "Default")
      (node (ref "IC301") (pin "9") (pinfunction "_DSR_9") (pintype "input"))
    )
    (net (code "114") (name "unconnected-(IC301-_DTR-Pad2)") (class "Default")
      (node (ref "IC301") (pin "2") (pinfunction "_DTR_2") (pintype "output"))
    )
    (net (code "115") (name "unconnected-(IC301-_RI-Pad6)") (class "Default")
      (node (ref "IC301") (pin "6") (pinfunction "_RI_6") (pintype "input"))
    )
    (net (code "116") (name "unconnected-(IC301-_RTS-Pad3)") (class "Default")
      (node (ref "IC301") (pin "3") (pinfunction "_RTS_3") (pintype "output"))
    )
    (net (code "117") (name "unconnected-(IC401-3V3OUT-Pad17)") (class "Default")
      (node (ref "IC401") (pin "17") (pinfunction "3V3OUT_17") (pintype "output"))
    )
    (net (code "118") (name "unconnected-(IC401-CBUS1-Pad22)") (class "Default")
      (node (ref "IC401") (pin "22") (pinfunction "CBUS1_22") (pintype "bidirectional"))
    )
    (net (code "119") (name "unconnected-(IC401-CBUS2-Pad13)") (class "Default")
      (node (ref "IC401") (pin "13") (pinfunction "CBUS2_13") (pintype "bidirectional"))
    )
    (net (code "120") (name "unconnected-(IC401-CBUS3-Pad14)") (class "Default")
      (node (ref "IC401") (pin "14") (pinfunction "CBUS3_14") (pintype "bidirectional"))
    )
    (net (code "121") (name "unconnected-(IC401-CBUS4-Pad12)") (class "Default")
      (node (ref "IC401") (pin "12") (pinfunction "CBUS4_12") (pintype "bidirectional"))
    )
    (net (code "122") (name "unconnected-(IC401-OSCI-Pad27)") (class "Default")
      (node (ref "IC401") (pin "27") (pinfunction "OSCI_27") (pintype "input"))
    )
    (net (code "123") (name "unconnected-(IC401-OSCO-Pad28)") (class "Default")
      (node (ref "IC401") (pin "28") (pinfunction "OSCO_28") (pintype "output"))
    )
    (net (code "124") (name "unconnected-(IC401-_CTS-Pad11)") (class "Default")
      (node (ref "IC401") (pin "11") (pinfunction "_CTS_11") (pintype "input"))
    )
    (net (code "125") (name "unconnected-(IC401-_DCD-Pad10)") (class "Default")
      (node (ref "IC401") (pin "10") (pinfunction "_DCD_10") (pintype "input"))
    )
    (net (code "126") (name "unconnected-(IC401-_DSR-Pad9)") (class "Default")
      (node (ref "IC401") (pin "9") (pinfunction "_DSR_9") (pintype "input"))
    )
    (net (code "127") (name "unconnected-(IC401-_DTR-Pad2)") (class "Default")
      (node (ref "IC401") (pin "2") (pinfunction "_DTR_2") (pintype "output"))
    )
    (net (code "128") (name "unconnected-(IC401-_RI-Pad6)") (class "Default")
      (node (ref "IC401") (pin "6") (pinfunction "_RI_6") (pintype "input"))
    )
    (net (code "129") (name "unconnected-(IC401-_RTS-Pad3)") (class "Default")
      (node (ref "IC401") (pin "3") (pinfunction "_RTS_3") (pintype "output"))
    )
    (net (code "130") (name "unconnected-(IC501-3V3OUT-Pad17)") (class "Default")
      (node (ref "IC501") (pin "17") (pinfunction "3V3OUT_17") (pintype "output"))
    )
    (net (code "131") (name "unconnected-(IC501-CBUS1-Pad22)") (class "Default")
      (node (ref "IC501") (pin "22") (pinfunction "CBUS1_22") (pintype "bidirectional"))
    )
    (net (code "132") (name "unconnected-(IC501-CBUS2-Pad13)") (class "Default")
      (node (ref "IC501") (pin "13") (pinfunction "CBUS2_13") (pintype "bidirectional"))
    )
    (net (code "133") (name "unconnected-(IC501-CBUS3-Pad14)") (class "Default")
      (node (ref "IC501") (pin "14") (pinfunction "CBUS3_14") (pintype "bidirectional"))
    )
    (net (code "134") (name "unconnected-(IC501-CBUS4-Pad12)") (class "Default")
      (node (ref "IC501") (pin "12") (pinfunction "CBUS4_12") (pintype "bidirectional"))
    )
    (net (code "135") (name "unconnected-(IC501-OSCI-Pad27)") (class "Default")
      (node (ref "IC501") (pin "27") (pinfunction "OSCI_27") (pintype "input"))
    )
    (net (code "136") (name "unconnected-(IC501-OSCO-Pad28)") (class "Default")
      (node (ref "IC501") (pin "28") (pinfunction "OSCO_28") (pintype "output"))
    )
    (net (code "137") (name "unconnected-(IC501-_CTS-Pad11)") (class "Default")
      (node (ref "IC501") (pin "11") (pinfunction "_CTS_11") (pintype "input"))
    )
    (net (code "138") (name "unconnected-(IC501-_DCD-Pad10)") (class "Default")
      (node (ref "IC501") (pin "10") (pinfunction "_DCD_10") (pintype "input"))
    )
    (net (code "139") (name "unconnected-(IC501-_DSR-Pad9)") (class "Default")
      (node (ref "IC501") (pin "9") (pinfunction "_DSR_9") (pintype "input"))
    )
    (net (code "140") (name "unconnected-(IC501-_DTR-Pad2)") (class "Default")
      (node (ref "IC501") (pin "2") (pinfunction "_DTR_2") (pintype "output"))
    )
    (net (code "141") (name "unconnected-(IC501-_RI-Pad6)") (class "Default")
      (node (ref "IC501") (pin "6") (pinfunction "_RI_6") (pintype "input"))
    )
    (net (code "142") (name "unconnected-(IC501-_RTS-Pad3)") (class "Default")
      (node (ref "IC501") (pin "3") (pinfunction "_RTS_3") (pintype "output"))
    )
    (net (code "143") (name "unconnected-(IC601-3V3OUT-Pad17)") (class "Default")
      (node (ref "IC601") (pin "17") (pinfunction "3V3OUT_17") (pintype "output"))
    )
    (net (code "144") (name "unconnected-(IC601-CBUS1-Pad22)") (class "Default")
      (node (ref "IC601") (pin "22") (pinfunction "CBUS1_22") (pintype "bidirectional"))
    )
    (net (code "145") (name "unconnected-(IC601-CBUS2-Pad13)") (class "Default")
      (node (ref "IC601") (pin "13") (pinfunction "CBUS2_13") (pintype "bidirectional"))
    )
    (net (code "146") (name "unconnected-(IC601-CBUS3-Pad14)") (class "Default")
      (node (ref "IC601") (pin "14") (pinfunction "CBUS3_14") (pintype "bidirectional"))
    )
    (net (code "147") (name "unconnected-(IC601-CBUS4-Pad12)") (class "Default")
      (node (ref "IC601") (pin "12") (pinfunction "CBUS4_12") (pintype "bidirectional"))
    )
    (net (code "148") (name "unconnected-(IC601-OSCI-Pad27)") (class "Default")
      (node (ref "IC601") (pin "27") (pinfunction "OSCI_27") (pintype "input"))
    )
    (net (code "149") (name "unconnected-(IC601-OSCO-Pad28)") (class "Default")
      (node (ref "IC601") (pin "28") (pinfunction "OSCO_28") (pintype "output"))
    )
    (net (code "150") (name "unconnected-(IC601-_CTS-Pad11)") (class "Default")
      (node (ref "IC601") (pin "11") (pinfunction "_CTS_11") (pintype "input"))
    )
    (net (code "151") (name "unconnected-(IC601-_DCD-Pad10)") (class "Default")
      (node (ref "IC601") (pin "10") (pinfunction "_DCD_10") (pintype "input"))
    )
    (net (code "152") (name "unconnected-(IC601-_DSR-Pad9)") (class "Default")
      (node (ref "IC601") (pin "9") (pinfunction "_DSR_9") (pintype "input"))
    )
    (net (code "153") (name "unconnected-(IC601-_DTR-Pad2)") (class "Default")
      (node (ref "IC601") (pin "2") (pinfunction "_DTR_2") (pintype "output"))
    )
    (net (code "154") (name "unconnected-(IC601-_RI-Pad6)") (class "Default")
      (node (ref "IC601") (pin "6") (pinfunction "_RI_6") (pintype "input"))
    )
    (net (code "155") (name "unconnected-(IC601-_RTS-Pad3)") (class "Default")
      (node (ref "IC601") (pin "3") (pinfunction "_RTS_3") (pintype "output"))
    )
  )
)
